# extension_board_0_2.net
KiCad netlist of a schematic drawn in EAGLE
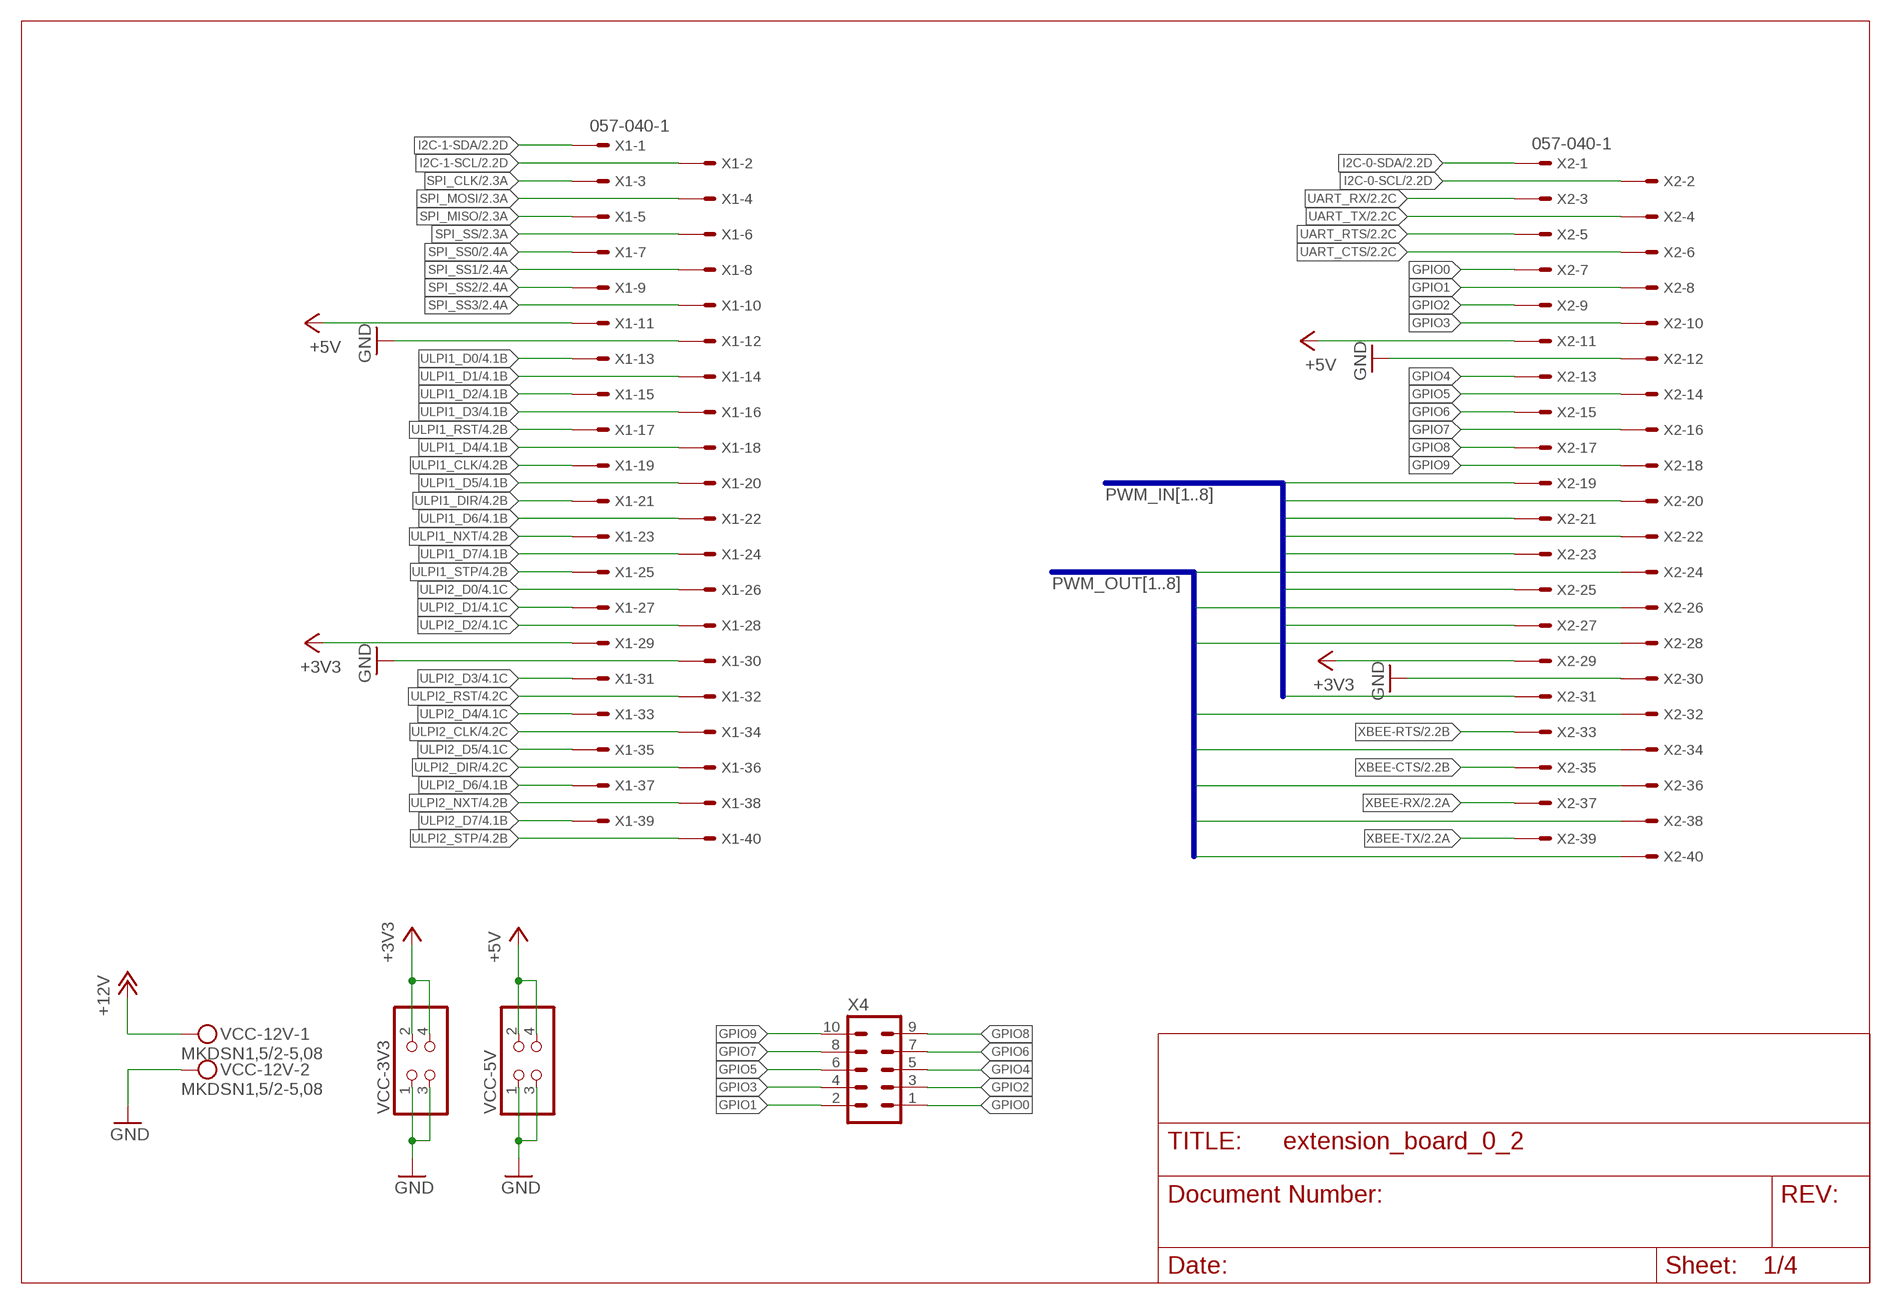
[diagram p0: schematic, sheet 1]
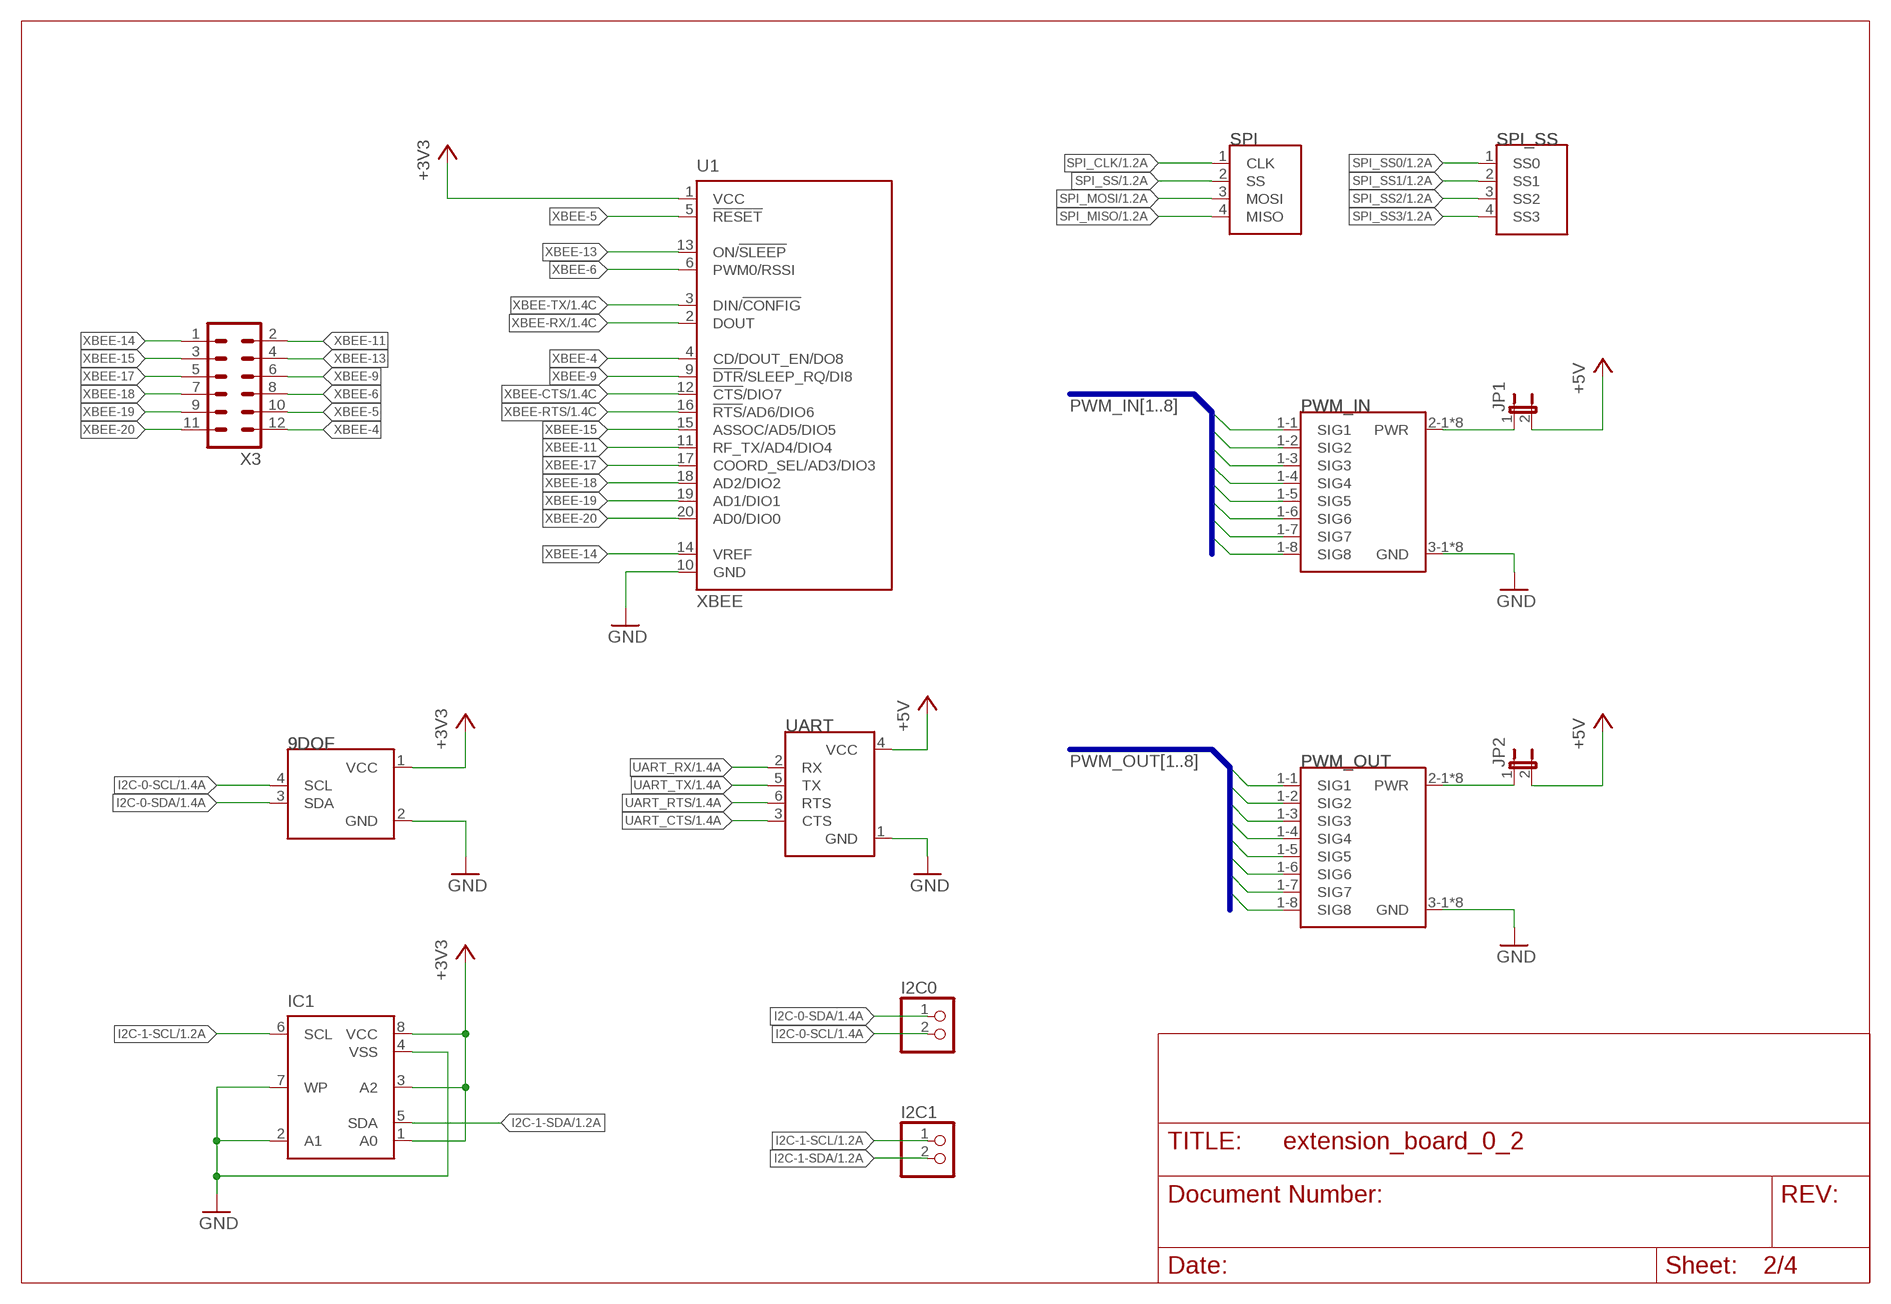
[diagram p1: schematic, sheet 2]
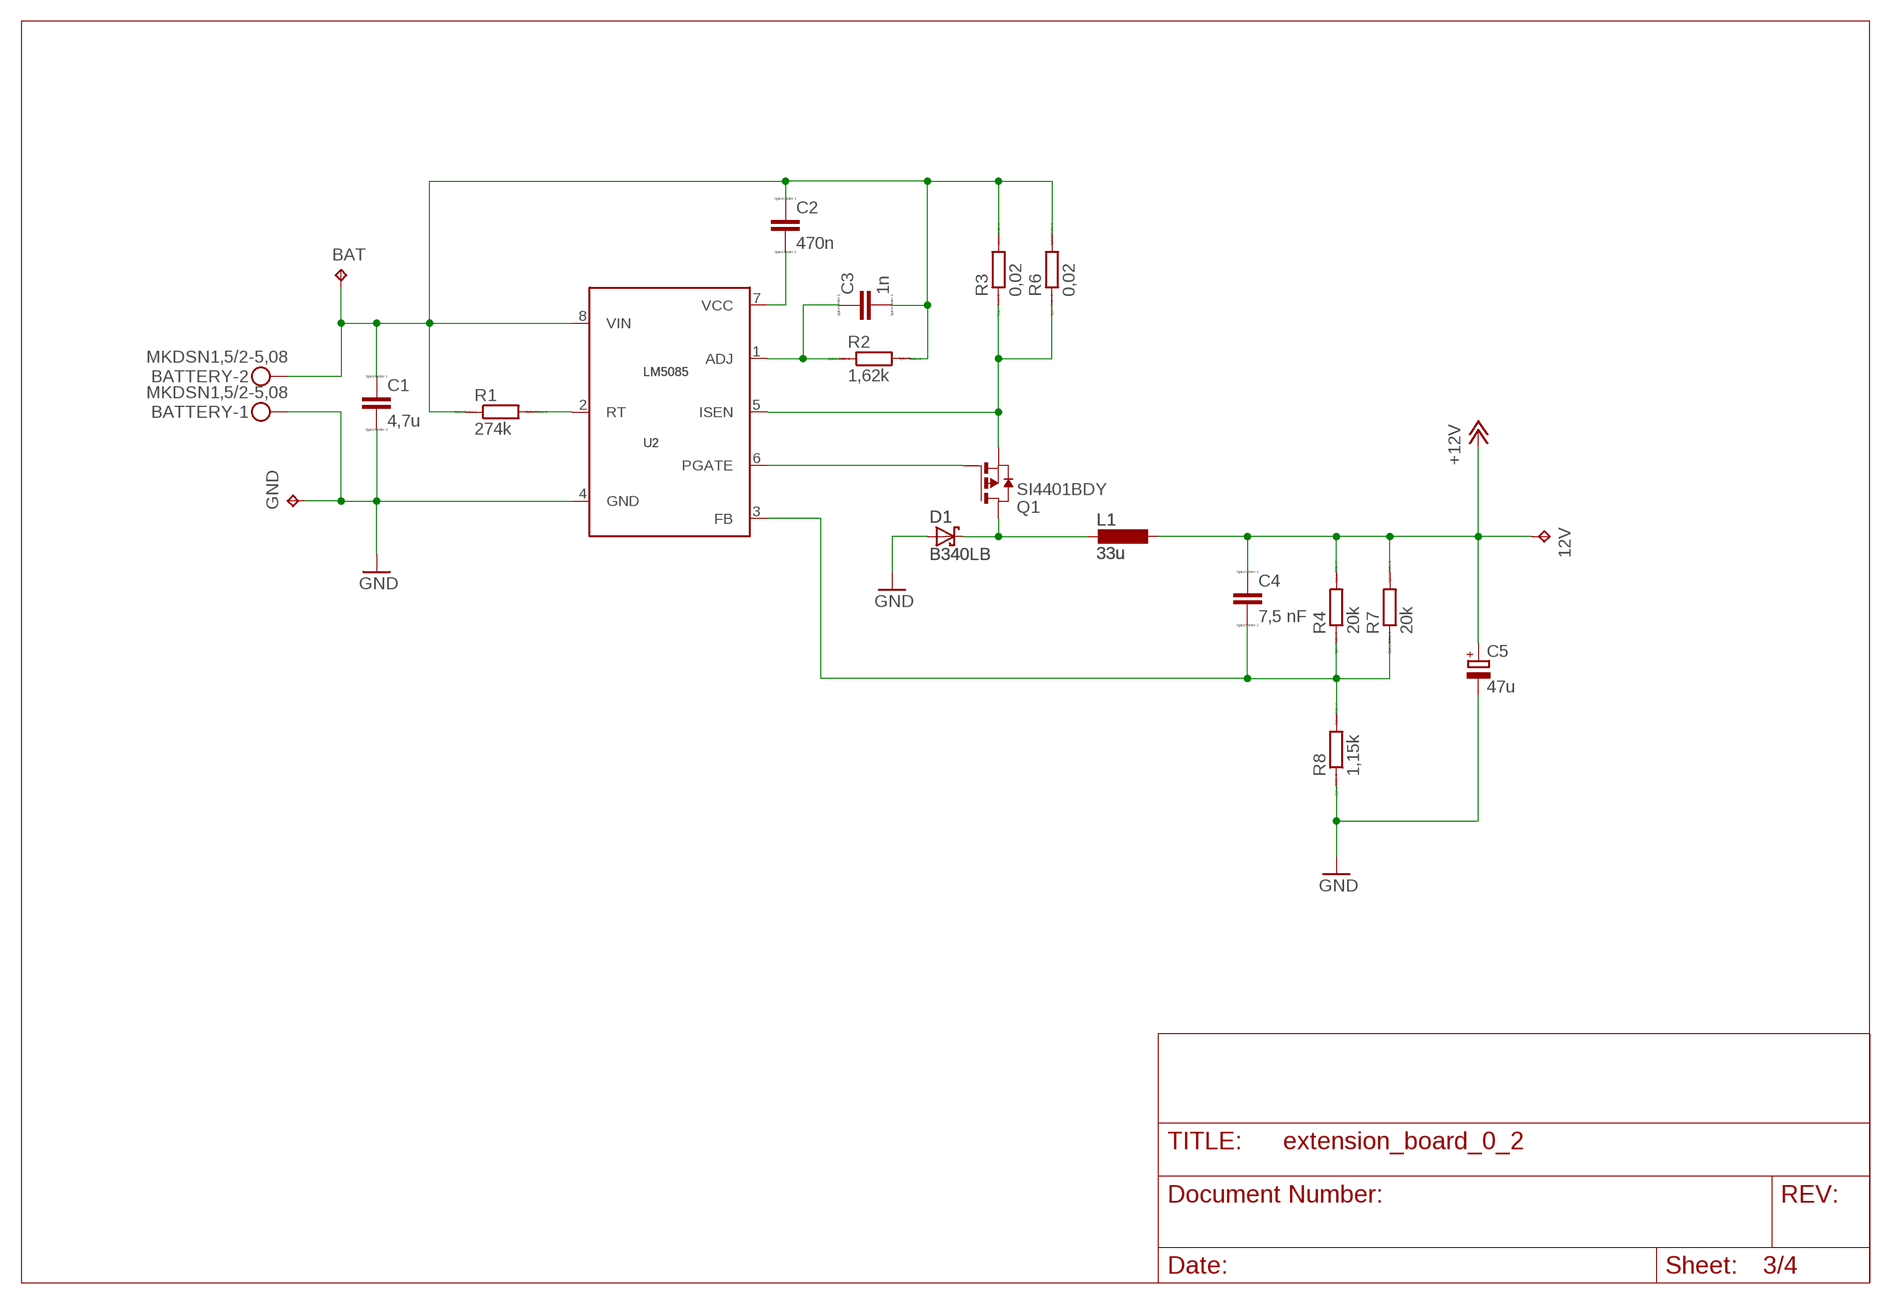
[diagram p2: schematic, sheet 3]
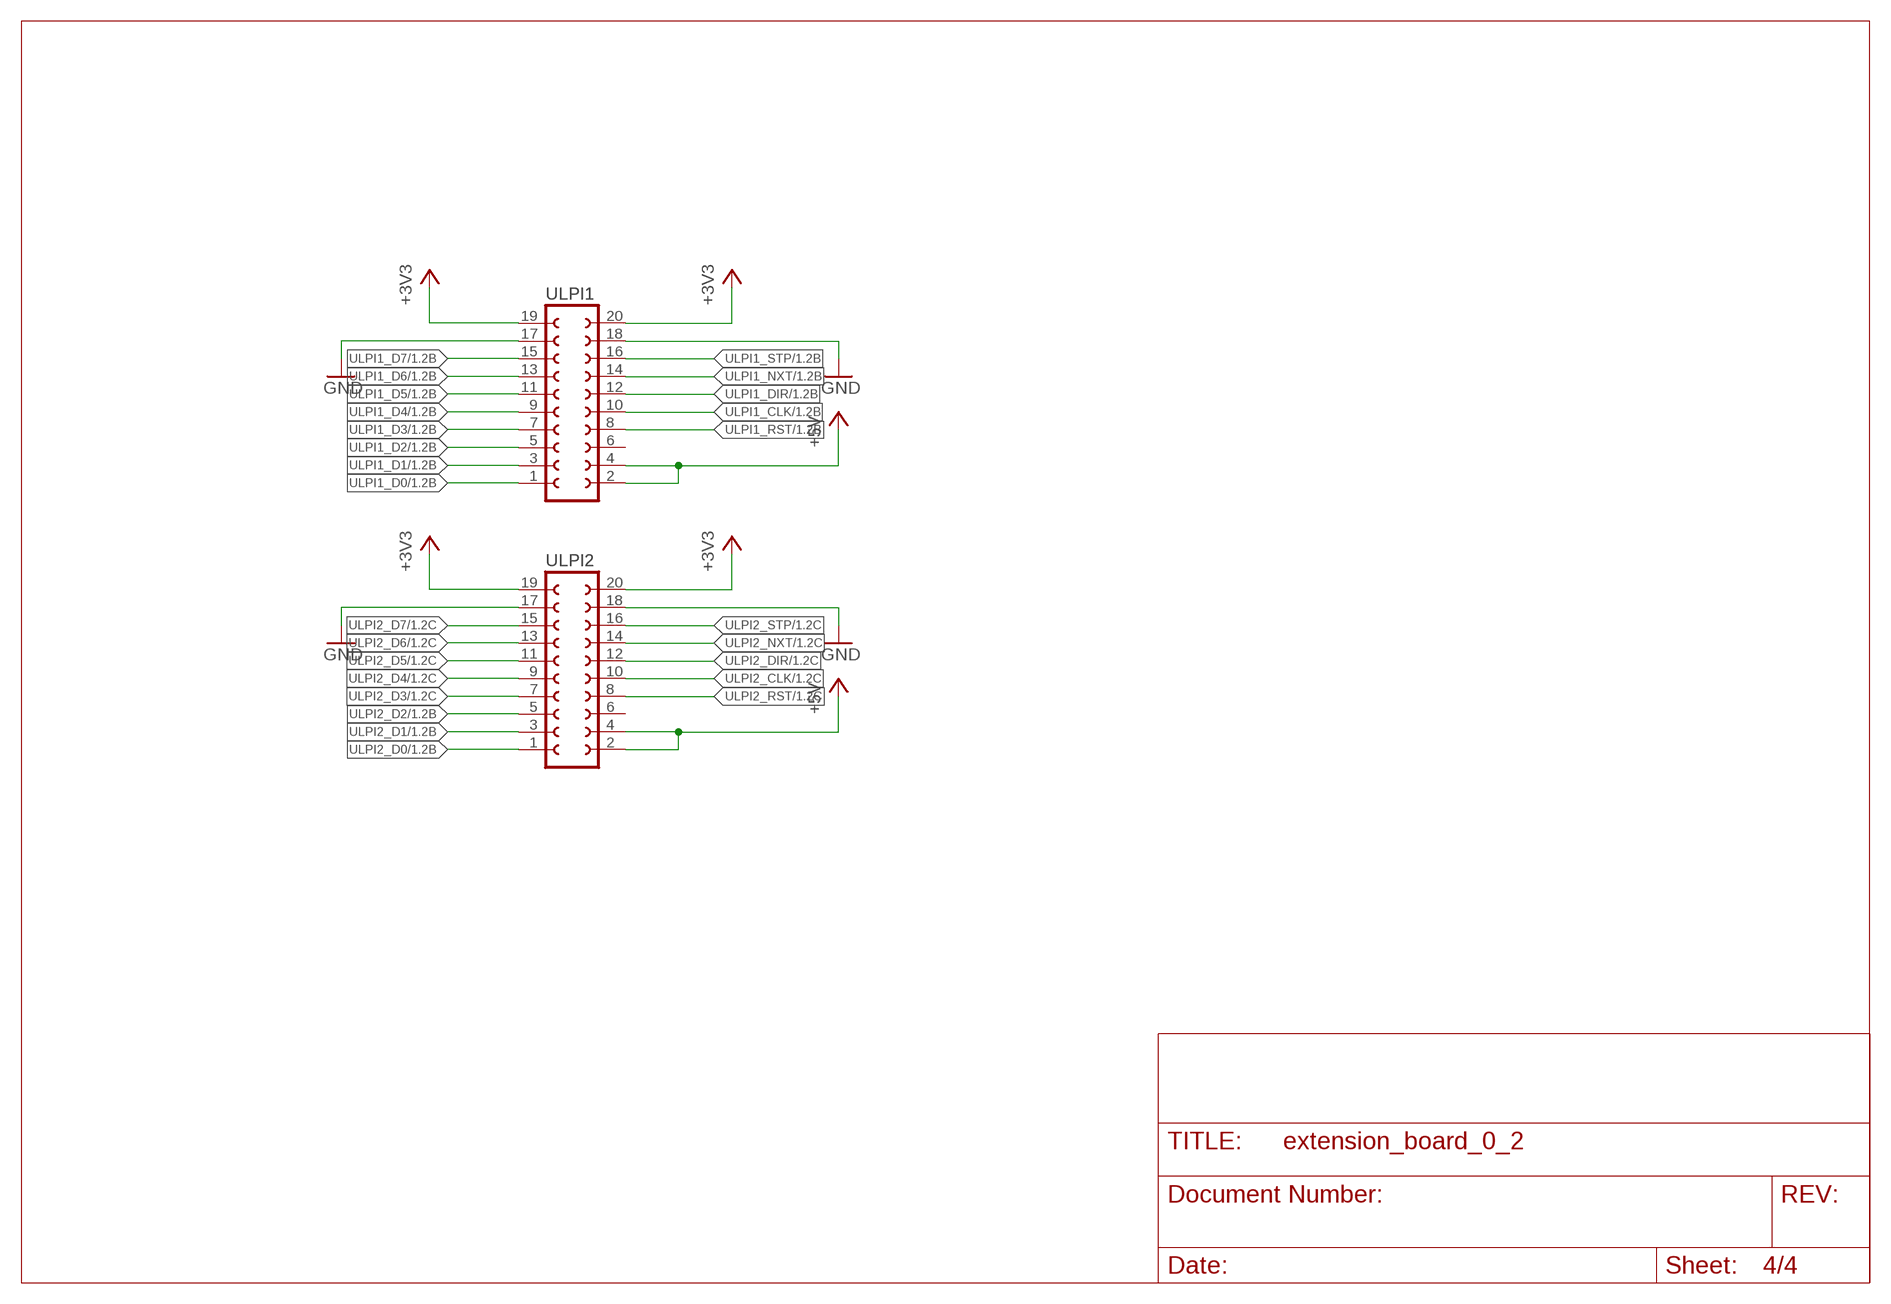
[diagram p3: schematic, sheet 4]

(export (version "E")
  (design (tool "Eeschema 10.0.6"))
  (components
    (comp (ref "9DOF")
      (value "I2C")
      (footprint "eagle-import:MA04-1")
      (libsource (lib "eagle-import") (part "I2C"))
    )
    (comp (ref "I2C0")
      (value "PINHD-1X2")
      (footprint "eagle-import:1X02")
      (libsource (lib "eagle-import") (part "PINHD-1X2"))
    )
    (comp (ref "I2C1")
      (value "PINHD-1X2")
      (footprint "eagle-import:1X02")
      (libsource (lib "eagle-import") (part "PINHD-1X2"))
    )
    (comp (ref "IC1")
      (value "NE555")
      (footprint "eagle-import:DIL-08")
      (libsource (lib "eagle-import") (part "NE555"))
    )
    (comp (ref "JP1")
      (value "JP1E")
      (footprint "eagle-import:JP1")
      (libsource (lib "eagle-import") (part "JP1E"))
    )
    (comp (ref "JP2")
      (value "JP1E")
      (footprint "eagle-import:JP1")
      (libsource (lib "eagle-import") (part "JP1E"))
    )
    (comp (ref "PWM_IN")
      (value "8RX")
      (footprint "eagle-import:MA08-3")
      (libsource (lib "eagle-import") (part "8RX"))
    )
    (comp (ref "PWM_OUT")
      (value "8RX")
      (footprint "eagle-import:MA08-3")
      (libsource (lib "eagle-import") (part "8RX"))
    )
    (comp (ref "SPI")
      (value "SPI_MAIN")
      (footprint "eagle-import:MA04-1")
      (libsource (lib "eagle-import") (part "SPI_MAIN"))
    )
    (comp (ref "SPI_SS")
      (value "SPI_SS")
      (footprint "eagle-import:MA04-1")
      (libsource (lib "eagle-import") (part "SPI_SS"))
    )
    (comp (ref "U1")
      (value "XBEE")
      (footprint "eagle-import:XBEE")
      (fields (field (name "MPN") "XBP24-Z7UIT-004"))
      (libsource (lib "eagle-import") (part "XBEE"))
    )
    (comp (ref "UART")
      (value "UART")
      (footprint "eagle-import:MA03-2")
      (libsource (lib "eagle-import") (part "UART"))
    )
    (comp (ref "X3")
      (value "MA06-2")
      (footprint "eagle-import:MA06-2")
      (libsource (lib "eagle-import") (part "MA06-2"))
    )
    (comp (ref "VCC-3V3")
      (value "PINHD-2X2")
      (footprint "eagle-import:2X02")
      (libsource (lib "eagle-import") (part "PINHD-2X2"))
    )
    (comp (ref "VCC-5V")
      (value "PINHD-2X2")
      (footprint "eagle-import:2X02")
      (libsource (lib "eagle-import") (part "PINHD-2X2"))
    )
    (comp (ref "VCC-12V")
      (value "MKDSN1,5/2-5,08")
      (footprint "eagle-import:MKDSN1,5_2-5,08")
      (fields (field (name "MPN") "MKDSN 1,5/2-5.08"))
      (libsource (lib "eagle-import") (part "MKDSN1,5/2-5,08"))
    )
    (comp (ref "X1")
      (value "057-040-1")
      (footprint "eagle-import:057-040-1")
      (libsource (lib "eagle-import") (part "057-040-1"))
    )
    (comp (ref "X2")
      (value "057-040-1")
      (footprint "eagle-import:057-040-1")
      (libsource (lib "eagle-import") (part "057-040-1"))
    )
    (comp (ref "X4")
      (value "MA05-2")
      (footprint "eagle-import:MA05-2")
      (libsource (lib "eagle-import") (part "MA05-2"))
    )
    (comp (ref "12V")
      (value "TPPAD1-13")
      (footprint "eagle-import:P1-13")
      (libsource (lib "eagle-import") (part "TPPAD1-13"))
    )
    (comp (ref "BAT")
      (value "TPPAD1-13")
      (footprint "eagle-import:P1-13")
      (libsource (lib "eagle-import") (part "TPPAD1-13"))
    )
    (comp (ref "BATTERY")
      (value "MKDSN1,5/2-5,08")
      (footprint "eagle-import:MKDSN1,5_2-5,08")
      (fields (field (name "MPN") "MKDSN 1,5/2-5.08"))
      (libsource (lib "eagle-import") (part "MKDSN1,5/2-5,08"))
    )
    (comp (ref "C1")
      (value "4,7u")
      (footprint "eagle-import:C0805")
      (libsource (lib "eagle-import") (part "C"))
    )
    (comp (ref "C2")
      (value "470n")
      (footprint "eagle-import:C1206")
      (libsource (lib "eagle-import") (part "CC1206"))
    )
    (comp (ref "C3")
      (value "1n")
      (footprint "eagle-import:C1206")
      (libsource (lib "eagle-import") (part "CC1206"))
    )
    (comp (ref "C4")
      (value "7,5 nF")
      (footprint "eagle-import:C0603")
      (libsource (lib "eagle-import") (part "CC0603"))
    )
    (comp (ref "C5")
      (value "47u")
      (footprint "eagle-import:CT3216")
      (libsource (lib "eagle-import") (part "CPOL-EUCT3216"))
    )
    (comp (ref "D1")
      (value "B340LB")
      (footprint "eagle-import:SMB")
      (libsource (lib "eagle-import") (part "B340LB"))
    )
    (comp (ref "GND")
      (value "TPPAD1-13")
      (footprint "eagle-import:P1-13")
      (libsource (lib "eagle-import") (part "TPPAD1-13"))
    )
    (comp (ref "L1")
      (value "33u")
      (footprint "eagle-import:INDUKTOR")
      (libsource (lib "eagle-import") (part "MSS1210"))
    )
    (comp (ref "Q1")
      (value "SI4401BDY")
      (footprint "eagle-import:SO8-FET")
      (libsource (lib "eagle-import") (part "SI4401BDY"))
    )
    (comp (ref "R1")
      (value "274k")
      (footprint "eagle-import:R1206")
      (libsource (lib "eagle-import") (part "RR1206"))
    )
    (comp (ref "R2")
      (value "1,62k")
      (footprint "eagle-import:R0805")
      (libsource (lib "eagle-import") (part "R"))
    )
    (comp (ref "R3")
      (value "0,02")
      (footprint "eagle-import:R1206")
      (libsource (lib "eagle-import") (part "RR1206"))
    )
    (comp (ref "R4")
      (value "20k")
      (footprint "eagle-import:R1206")
      (libsource (lib "eagle-import") (part "RR1206"))
    )
    (comp (ref "R6")
      (value "0,02")
      (footprint "eagle-import:R1206")
      (libsource (lib "eagle-import") (part "RR1206"))
    )
    (comp (ref "R7")
      (value "20k")
      (footprint "eagle-import:R1206")
      (libsource (lib "eagle-import") (part "RR1206"))
    )
    (comp (ref "R8")
      (value "1,15k")
      (footprint "eagle-import:R0805")
      (libsource (lib "eagle-import") (part "R"))
    )
    (comp (ref "U2")
      (value "LM5085")
      (footprint "eagle-import:S-PDSO-G08")
      (libsource (lib "eagle-import") (part "LM5085"))
    )
    (comp (ref "ULPI1")
      (value "FE10-2W")
      (footprint "eagle-import:FE10-2W")
      (libsource (lib "eagle-import") (part "FE10-2W"))
    )
    (comp (ref "ULPI2")
      (value "FE10-2W")
      (footprint "eagle-import:FE10-2W")
      (libsource (lib "eagle-import") (part "FE10-2W"))
    )
  )
  (nets
    (net (code "1") (name "+3V3") (class "Default")
      (node (ref "9DOF") (pin "1") (pinfunction "VCC_1") (pintype "power_in"))
      (node (ref "IC1") (pin "1") (pinfunction "A0_1") (pintype "input"))
      (node (ref "IC1") (pin "3") (pinfunction "A2_3") (pintype "input"))
      (node (ref "IC1") (pin "8") (pinfunction "VCC_8") (pintype "power_in"))
      (node (ref "U1") (pin "1") (pinfunction "VCC_1") (pintype "power_in"))
      (node (ref "ULPI1") (pin "19") (pinfunction "19_19") (pintype "passive"))
      (node (ref "ULPI1") (pin "20") (pinfunction "20_20") (pintype "passive"))
      (node (ref "ULPI2") (pin "19") (pinfunction "19_19") (pintype "passive"))
      (node (ref "ULPI2") (pin "20") (pinfunction "20_20") (pintype "passive"))
      (node (ref "VCC-3V3") (pin "2") (pinfunction "2_2") (pintype "passive"))
      (node (ref "VCC-3V3") (pin "4") (pinfunction "4_4") (pintype "passive"))
      (node (ref "X1") (pin "29") (pinfunction "S_29") (pintype "passive"))
      (node (ref "X2") (pin "29") (pinfunction "S_29") (pintype "passive"))
    )
    (net (code "2") (name "+5V") (class "Default")
      (node (ref "JP1") (pin "2") (pinfunction "2_2") (pintype "passive"))
      (node (ref "JP2") (pin "2") (pinfunction "2_2") (pintype "passive"))
      (node (ref "UART") (pin "4") (pinfunction "VCC_4") (pintype "bidirectional"))
      (node (ref "ULPI1") (pin "2") (pinfunction "2_2") (pintype "passive"))
      (node (ref "ULPI1") (pin "4") (pinfunction "4_4") (pintype "passive"))
      (node (ref "ULPI2") (pin "2") (pinfunction "2_2") (pintype "passive"))
      (node (ref "ULPI2") (pin "4") (pinfunction "4_4") (pintype "passive"))
      (node (ref "VCC-5V") (pin "2") (pinfunction "2_2") (pintype "passive"))
      (node (ref "VCC-5V") (pin "4") (pinfunction "4_4") (pintype "passive"))
      (node (ref "X1") (pin "11") (pinfunction "S_11") (pintype "passive"))
      (node (ref "X2") (pin "11") (pinfunction "S_11") (pintype "passive"))
    )
    (net (code "3") (name "+12V") (class "Default")
      (node (ref "12V") (pin "TP") (pinfunction "TP_TP") (pintype "input"))
      (node (ref "C4") (pin "1") (pinfunction "1_1") (pintype "passive"))
      (node (ref "C5") (pin "+") (pinfunction "+_+") (pintype "passive"))
      (node (ref "L1") (pin "P$2") (pinfunction "2_P$2") (pintype "passive"))
      (node (ref "R4") (pin "2") (pinfunction "2_2") (pintype "passive"))
      (node (ref "R7") (pin "2") (pinfunction "2_2") (pintype "passive"))
      (node (ref "VCC-12V") (pin "1") (pinfunction "KL_1") (pintype "passive"))
    )
    (net (code "8") (name "GND") (class "Default")
      (node (ref "9DOF") (pin "2") (pinfunction "GND_2") (pintype "power_in"))
      (node (ref "BATTERY") (pin "1") (pinfunction "KL_1") (pintype "passive"))
      (node (ref "C1") (pin "2") (pinfunction "2_2") (pintype "passive"))
      (node (ref "C5") (pin "-") (pinfunction "-_-") (pintype "passive"))
      (node (ref "D1") (pin "A") (pinfunction "A_A") (pintype "passive"))
      (node (ref "GND") (pin "TP") (pinfunction "TP_TP") (pintype "input"))
      (node (ref "IC1") (pin "2") (pinfunction "A1_2") (pintype "input"))
      (node (ref "IC1") (pin "4") (pinfunction "VSS_4") (pintype "power_in"))
      (node (ref "IC1") (pin "7") (pinfunction "WP_7") (pintype "input"))
      (node (ref "PWM_IN") (pin "3-1") (pinfunction "GND_3-1") (pintype "power_in"))
      (node (ref "PWM_IN") (pin "3-2") (pinfunction "GND_3-2") (pintype "power_in"))
      (node (ref "PWM_IN") (pin "3-3") (pinfunction "GND_3-3") (pintype "power_in"))
      (node (ref "PWM_IN") (pin "3-4") (pinfunction "GND_3-4") (pintype "power_in"))
      (node (ref "PWM_IN") (pin "3-5") (pinfunction "GND_3-5") (pintype "power_in"))
      (node (ref "PWM_IN") (pin "3-6") (pinfunction "GND_3-6") (pintype "power_in"))
      (node (ref "PWM_IN") (pin "3-7") (pinfunction "GND_3-7") (pintype "power_in"))
      (node (ref "PWM_IN") (pin "3-8") (pinfunction "GND_3-8") (pintype "power_in"))
      (node (ref "PWM_OUT") (pin "3-1") (pinfunction "GND_3-1") (pintype "power_in"))
      (node (ref "PWM_OUT") (pin "3-2") (pinfunction "GND_3-2") (pintype "power_in"))
      (node (ref "PWM_OUT") (pin "3-3") (pinfunction "GND_3-3") (pintype "power_in"))
      (node (ref "PWM_OUT") (pin "3-4") (pinfunction "GND_3-4") (pintype "power_in"))
      (node (ref "PWM_OUT") (pin "3-5") (pinfunction "GND_3-5") (pintype "power_in"))
      (node (ref "PWM_OUT") (pin "3-6") (pinfunction "GND_3-6") (pintype "power_in"))
      (node (ref "PWM_OUT") (pin "3-7") (pinfunction "GND_3-7") (pintype "power_in"))
      (node (ref "PWM_OUT") (pin "3-8") (pinfunction "GND_3-8") (pintype "power_in"))
      (node (ref "R8") (pin "1") (pinfunction "1_1") (pintype "passive"))
      (node (ref "U1") (pin "10") (pinfunction "GND_10") (pintype "power_in"))
      (node (ref "U2") (pin "4") (pinfunction "GND_4") (pintype "power_in"))
      (node (ref "UART") (pin "1") (pinfunction "GND_1") (pintype "bidirectional"))
      (node (ref "ULPI1") (pin "17") (pinfunction "17_17") (pintype "passive"))
      (node (ref "ULPI1") (pin "18") (pinfunction "18_18") (pintype "passive"))
      (node (ref "ULPI2") (pin "17") (pinfunction "17_17") (pintype "passive"))
      (node (ref "ULPI2") (pin "18") (pinfunction "18_18") (pintype "passive"))
      (node (ref "VCC-12V") (pin "2") (pinfunction "KL_2") (pintype "passive"))
      (node (ref "VCC-3V3") (pin "1") (pinfunction "1_1") (pintype "passive"))
      (node (ref "VCC-3V3") (pin "3") (pinfunction "3_3") (pintype "passive"))
      (node (ref "VCC-5V") (pin "1") (pinfunction "1_1") (pintype "passive"))
      (node (ref "VCC-5V") (pin "3") (pinfunction "3_3") (pintype "passive"))
      (node (ref "X1") (pin "12") (pinfunction "S_12") (pintype "passive"))
      (node (ref "X1") (pin "30") (pinfunction "S_30") (pintype "passive"))
      (node (ref "X2") (pin "12") (pinfunction "S_12") (pintype "passive"))
      (node (ref "X2") (pin "30") (pinfunction "S_30") (pintype "passive"))
    )
    (net (code "9") (name "GPIO0") (class "Default")
      (node (ref "X2") (pin "7") (pinfunction "S_7") (pintype "passive"))
      (node (ref "X4") (pin "1") (pinfunction "1_1") (pintype "passive"))
    )
    (net (code "10") (name "GPIO1") (class "Default")
      (node (ref "X2") (pin "8") (pinfunction "S_8") (pintype "passive"))
      (node (ref "X4") (pin "2") (pinfunction "2_2") (pintype "passive"))
    )
    (net (code "11") (name "GPIO2") (class "Default")
      (node (ref "X2") (pin "9") (pinfunction "S_9") (pintype "passive"))
      (node (ref "X4") (pin "3") (pinfunction "3_3") (pintype "passive"))
    )
    (net (code "12") (name "GPIO3") (class "Default")
      (node (ref "X2") (pin "10") (pinfunction "S_10") (pintype "passive"))
      (node (ref "X4") (pin "4") (pinfunction "4_4") (pintype "passive"))
    )
    (net (code "13") (name "GPIO4") (class "Default")
      (node (ref "X2") (pin "13") (pinfunction "S_13") (pintype "passive"))
      (node (ref "X4") (pin "5") (pinfunction "5_5") (pintype "passive"))
    )
    (net (code "14") (name "GPIO5") (class "Default")
      (node (ref "X2") (pin "14") (pinfunction "S_14") (pintype "passive"))
      (node (ref "X4") (pin "6") (pinfunction "6_6") (pintype "passive"))
    )
    (net (code "15") (name "GPIO6") (class "Default")
      (node (ref "X2") (pin "15") (pinfunction "S_15") (pintype "passive"))
      (node (ref "X4") (pin "7") (pinfunction "7_7") (pintype "passive"))
    )
    (net (code "16") (name "GPIO7") (class "Default")
      (node (ref "X2") (pin "16") (pinfunction "S_16") (pintype "passive"))
      (node (ref "X4") (pin "8") (pinfunction "8_8") (pintype "passive"))
    )
    (net (code "17") (name "GPIO8") (class "Default")
      (node (ref "X2") (pin "17") (pinfunction "S_17") (pintype "passive"))
      (node (ref "X4") (pin "9") (pinfunction "9_9") (pintype "passive"))
    )
    (net (code "18") (name "GPIO9") (class "Default")
      (node (ref "X2") (pin "18") (pinfunction "S_18") (pintype "passive"))
      (node (ref "X4") (pin "10") (pinfunction "10_10") (pintype "passive"))
    )
    (net (code "19") (name "I2C-0-SCL") (class "Default")
      (node (ref "9DOF") (pin "4") (pinfunction "SCL_4") (pintype "bidirectional"))
      (node (ref "I2C0") (pin "2") (pinfunction "2_2") (pintype "passive"))
      (node (ref "X2") (pin "2") (pinfunction "S_2") (pintype "passive"))
    )
    (net (code "20") (name "I2C-0-SDA") (class "Default")
      (node (ref "9DOF") (pin "3") (pinfunction "SDA_3") (pintype "bidirectional"))
      (node (ref "I2C0") (pin "1") (pinfunction "1_1") (pintype "passive"))
      (node (ref "X2") (pin "1") (pinfunction "S_1") (pintype "passive"))
    )
    (net (code "21") (name "I2C-1-SCL") (class "Default")
      (node (ref "I2C1") (pin "1") (pinfunction "1_1") (pintype "passive"))
      (node (ref "IC1") (pin "6") (pinfunction "SCL_6") (pintype "bidirectional"))
      (node (ref "X1") (pin "2") (pinfunction "S_2") (pintype "passive"))
    )
    (net (code "22") (name "I2C-1-SDA") (class "Default")
      (node (ref "I2C1") (pin "2") (pinfunction "2_2") (pintype "passive"))
      (node (ref "IC1") (pin "5") (pinfunction "SDA_5") (pintype "bidirectional"))
      (node (ref "X1") (pin "1") (pinfunction "S_1") (pintype "passive"))
    )
    (net (code "23") (name "Net-(BATTERYB-KL)") (class "Default")
      (node (ref "BAT") (pin "TP") (pinfunction "TP_TP") (pintype "input"))
      (node (ref "BATTERY") (pin "2") (pinfunction "KL_2") (pintype "passive"))
      (node (ref "C1") (pin "1") (pinfunction "1_1") (pintype "passive"))
      (node (ref "C2") (pin "1") (pinfunction "1_1") (pintype "passive"))
      (node (ref "C3") (pin "2") (pinfunction "2_2") (pintype "passive"))
      (node (ref "R1") (pin "1") (pinfunction "1_1") (pintype "passive"))
      (node (ref "R2") (pin "2") (pinfunction "2_2") (pintype "passive"))
      (node (ref "R3") (pin "2") (pinfunction "2_2") (pintype "passive"))
      (node (ref "R6") (pin "2") (pinfunction "2_2") (pintype "passive"))
      (node (ref "U2") (pin "8") (pinfunction "VIN_8") (pintype "input"))
    )
    (net (code "24") (name "Net-(JP1-Pad1)") (class "Default")
      (node (ref "JP1") (pin "1") (pinfunction "1_1") (pintype "passive"))
      (node (ref "PWM_IN") (pin "2-1") (pinfunction "PWR_2-1") (pintype "power_in"))
      (node (ref "PWM_IN") (pin "2-2") (pinfunction "PWR_2-2") (pintype "power_in"))
      (node (ref "PWM_IN") (pin "2-3") (pinfunction "PWR_2-3") (pintype "power_in"))
      (node (ref "PWM_IN") (pin "2-4") (pinfunction "PWR_2-4") (pintype "power_in"))
      (node (ref "PWM_IN") (pin "2-5") (pinfunction "PWR_2-5") (pintype "power_in"))
      (node (ref "PWM_IN") (pin "2-6") (pinfunction "PWR_2-6") (pintype "power_in"))
      (node (ref "PWM_IN") (pin "2-7") (pinfunction "PWR_2-7") (pintype "power_in"))
      (node (ref "PWM_IN") (pin "2-8") (pinfunction "PWR_2-8") (pintype "power_in"))
    )
    (net (code "25") (name "Net-(JP2-Pad1)") (class "Default")
      (node (ref "JP2") (pin "1") (pinfunction "1_1") (pintype "passive"))
      (node (ref "PWM_OUT") (pin "2-1") (pinfunction "PWR_2-1") (pintype "power_in"))
      (node (ref "PWM_OUT") (pin "2-2") (pinfunction "PWR_2-2") (pintype "power_in"))
      (node (ref "PWM_OUT") (pin "2-3") (pinfunction "PWR_2-3") (pintype "power_in"))
      (node (ref "PWM_OUT") (pin "2-4") (pinfunction "PWR_2-4") (pintype "power_in"))
      (node (ref "PWM_OUT") (pin "2-5") (pinfunction "PWR_2-5") (pintype "power_in"))
      (node (ref "PWM_OUT") (pin "2-6") (pinfunction "PWR_2-6") (pintype "power_in"))
      (node (ref "PWM_OUT") (pin "2-7") (pinfunction "PWR_2-7") (pintype "power_in"))
      (node (ref "PWM_OUT") (pin "2-8") (pinfunction "PWR_2-8") (pintype "power_in"))
    )
    (net (code "26") (name "Net-(L1-1)") (class "Default")
      (node (ref "D1") (pin "C") (pinfunction "C_C") (pintype "passive"))
      (node (ref "L1") (pin "P$1") (pinfunction "1_P$1") (pintype "passive"))
      (node (ref "Q1") (pin "5") (pinfunction "D_5") (pintype "passive"))
      (node (ref "Q1") (pin "6") (pinfunction "D_6") (pintype "passive"))
      (node (ref "Q1") (pin "7") (pinfunction "D_7") (pintype "passive"))
      (node (ref "Q1") (pin "8") (pinfunction "D_8") (pintype "passive"))
      (node (ref "Q1") (pin "D1") (pinfunction "D_D1") (pintype "passive"))
      (node (ref "Q1") (pin "D2") (pinfunction "D_D2") (pintype "passive"))
      (node (ref "Q1") (pin "D3") (pinfunction "D_D3") (pintype "passive"))
    )
    (net (code "27") (name "Net-(Q1-G)") (class "Default")
      (node (ref "Q1") (pin "4") (pinfunction "G_4") (pintype "passive"))
      (node (ref "U2") (pin "6") (pinfunction "PGATE_6") (pintype "bidirectional"))
    )
    (net (code "28") (name "Net-(U2-ADJ)") (class "Default")
      (node (ref "C3") (pin "1") (pinfunction "1_1") (pintype "passive"))
      (node (ref "R2") (pin "1") (pinfunction "1_1") (pintype "passive"))
      (node (ref "U2") (pin "1") (pinfunction "ADJ_1") (pintype "bidirectional"))
    )
    (net (code "29") (name "Net-(U2-FB)") (class "Default")
      (node (ref "C4") (pin "2") (pinfunction "2_2") (pintype "passive"))
      (node (ref "R4") (pin "1") (pinfunction "1_1") (pintype "passive"))
      (node (ref "R7") (pin "1") (pinfunction "1_1") (pintype "passive"))
      (node (ref "R8") (pin "2") (pinfunction "2_2") (pintype "passive"))
      (node (ref "U2") (pin "3") (pinfunction "FB_3") (pintype "bidirectional"))
    )
    (net (code "30") (name "Net-(U2-ISEN)") (class "Default")
      (node (ref "Q1") (pin "1") (pinfunction "S_1") (pintype "passive"))
      (node (ref "Q1") (pin "2") (pinfunction "S_2") (pintype "passive"))
      (node (ref "Q1") (pin "3") (pinfunction "S_3") (pintype "passive"))
      (node (ref "R3") (pin "1") (pinfunction "1_1") (pintype "passive"))
      (node (ref "R6") (pin "1") (pinfunction "1_1") (pintype "passive"))
      (node (ref "U2") (pin "5") (pinfunction "ISEN_5") (pintype "bidirectional"))
    )
    (net (code "31") (name "Net-(U2-RT)") (class "Default")
      (node (ref "R1") (pin "2") (pinfunction "2_2") (pintype "passive"))
      (node (ref "U2") (pin "2") (pinfunction "RT_2") (pintype "bidirectional"))
    )
    (net (code "32") (name "Net-(U2-VCC)") (class "Default")
      (node (ref "C2") (pin "2") (pinfunction "2_2") (pintype "passive"))
      (node (ref "U2") (pin "7") (pinfunction "VCC_7") (pintype "power_in"))
    )
    (net (code "33") (name "PWM_IN1") (class "Default")
      (node (ref "PWM_IN") (pin "1-1") (pinfunction "SIG1_1-1") (pintype "bidirectional"))
      (node (ref "X2") (pin "19") (pinfunction "S_19") (pintype "passive"))
    )
    (net (code "34") (name "PWM_IN2") (class "Default")
      (node (ref "PWM_IN") (pin "1-2") (pinfunction "SIG2_1-2") (pintype "bidirectional"))
      (node (ref "X2") (pin "20") (pinfunction "S_20") (pintype "passive"))
    )
    (net (code "35") (name "PWM_IN3") (class "Default")
      (node (ref "PWM_IN") (pin "1-3") (pinfunction "SIG3_1-3") (pintype "bidirectional"))
      (node (ref "X2") (pin "21") (pinfunction "S_21") (pintype "passive"))
    )
    (net (code "36") (name "PWM_IN4") (class "Default")
      (node (ref "PWM_IN") (pin "1-4") (pinfunction "SIG4_1-4") (pintype "bidirectional"))
      (node (ref "X2") (pin "22") (pinfunction "S_22") (pintype "passive"))
    )
    (net (code "37") (name "PWM_IN5") (class "Default")
      (node (ref "PWM_IN") (pin "1-5") (pinfunction "SIG5_1-5") (pintype "bidirectional"))
      (node (ref "X2") (pin "23") (pinfunction "S_23") (pintype "passive"))
    )
    (net (code "38") (name "PWM_IN6") (class "Default")
      (node (ref "PWM_IN") (pin "1-6") (pinfunction "SIG6_1-6") (pintype "bidirectional"))
      (node (ref "X2") (pin "25") (pinfunction "S_25") (pintype "passive"))
    )
    (net (code "39") (name "PWM_IN7") (class "Default")
      (node (ref "PWM_IN") (pin "1-7") (pinfunction "SIG7_1-7") (pintype "bidirectional"))
      (node (ref "X2") (pin "27") (pinfunction "S_27") (pintype "passive"))
    )
    (net (code "40") (name "PWM_IN8") (class "Default")
      (node (ref "PWM_IN") (pin "1-8") (pinfunction "SIG8_1-8") (pintype "bidirectional"))
      (node (ref "X2") (pin "31") (pinfunction "S_31") (pintype "passive"))
    )
    (net (code "41") (name "PWM_OUT1") (class "Default")
      (node (ref "PWM_OUT") (pin "1-1") (pinfunction "SIG1_1-1") (pintype "bidirectional"))
      (node (ref "X2") (pin "40") (pinfunction "S_40") (pintype "passive"))
    )
    (net (code "42") (name "PWM_OUT2") (class "Default")
      (node (ref "PWM_OUT") (pin "1-2") (pinfunction "SIG2_1-2") (pintype "bidirectional"))
      (node (ref "X2") (pin "38") (pinfunction "S_38") (pintype "passive"))
    )
    (net (code "43") (name "PWM_OUT3") (class "Default")
      (node (ref "PWM_OUT") (pin "1-3") (pinfunction "SIG3_1-3") (pintype "bidirectional"))
      (node (ref "X2") (pin "36") (pinfunction "S_36") (pintype "passive"))
    )
    (net (code "44") (name "PWM_OUT4") (class "Default")
      (node (ref "PWM_OUT") (pin "1-4") (pinfunction "SIG4_1-4") (pintype "bidirectional"))
      (node (ref "X2") (pin "34") (pinfunction "S_34") (pintype "passive"))
    )
    (net (code "45") (name "PWM_OUT5") (class "Default")
      (node (ref "PWM_OUT") (pin "1-5") (pinfunction "SIG5_1-5") (pintype "bidirectional"))
      (node (ref "X2") (pin "32") (pinfunction "S_32") (pintype "passive"))
    )
    (net (code "46") (name "PWM_OUT6") (class "Default")
      (node (ref "PWM_OUT") (pin "1-6") (pinfunction "SIG6_1-6") (pintype "bidirectional"))
      (node (ref "X2") (pin "28") (pinfunction "S_28") (pintype "passive"))
    )
    (net (code "47") (name "PWM_OUT7") (class "Default")
      (node (ref "PWM_OUT") (pin "1-7") (pinfunction "SIG7_1-7") (pintype "bidirectional"))
      (node (ref "X2") (pin "26") (pinfunction "S_26") (pintype "passive"))
    )
    (net (code "48") (name "PWM_OUT8") (class "Default")
      (node (ref "PWM_OUT") (pin "1-8") (pinfunction "SIG8_1-8") (pintype "bidirectional"))
      (node (ref "X2") (pin "24") (pinfunction "S_24") (pintype "passive"))
    )
    (net (code "49") (name "SPI_CLK") (class "Default")
      (node (ref "SPI") (pin "1") (pinfunction "CLK_1") (pintype "bidirectional"))
      (node (ref "X1") (pin "3") (pinfunction "S_3") (pintype "passive"))
    )
    (net (code "50") (name "SPI_MISO") (class "Default")
      (node (ref "SPI") (pin "4") (pinfunction "MISO_4") (pintype "bidirectional"))
      (node (ref "X1") (pin "5") (pinfunction "S_5") (pintype "passive"))
    )
    (net (code "51") (name "SPI_MOSI") (class "Default")
      (node (ref "SPI") (pin "3") (pinfunction "MOSI_3") (pintype "bidirectional"))
      (node (ref "X1") (pin "4") (pinfunction "S_4") (pintype "passive"))
    )
    (net (code "52") (name "SPI_SS") (class "Default")
      (node (ref "SPI") (pin "2") (pinfunction "SS_2") (pintype "bidirectional"))
      (node (ref "X1") (pin "6") (pinfunction "S_6") (pintype "passive"))
    )
    (net (code "53") (name "SPI_SS0") (class "Default")
      (node (ref "SPI_SS") (pin "1") (pinfunction "SS0_1") (pintype "bidirectional"))
      (node (ref "X1") (pin "7") (pinfunction "S_7") (pintype "passive"))
    )
    (net (code "54") (name "SPI_SS1") (class "Default")
      (node (ref "SPI_SS") (pin "2") (pinfunction "SS1_2") (pintype "bidirectional"))
      (node (ref "X1") (pin "8") (pinfunction "S_8") (pintype "passive"))
    )
    (net (code "55") (name "SPI_SS2") (class "Default")
      (node (ref "SPI_SS") (pin "3") (pinfunction "SS2_3") (pintype "bidirectional"))
      (node (ref "X1") (pin "9") (pinfunction "S_9") (pintype "passive"))
    )
    (net (code "56") (name "SPI_SS3") (class "Default")
      (node (ref "SPI_SS") (pin "4") (pinfunction "SS3_4") (pintype "bidirectional"))
      (node (ref "X1") (pin "10") (pinfunction "S_10") (pintype "passive"))
    )
    (net (code "57") (name "UART_CTS") (class "Default")
      (node (ref "UART") (pin "3") (pinfunction "CTS_3") (pintype "bidirectional"))
      (node (ref "X2") (pin "6") (pinfunction "S_6") (pintype "passive"))
    )
    (net (code "58") (name "UART_RTS") (class "Default")
      (node (ref "UART") (pin "6") (pinfunction "RTS_6") (pintype "bidirectional"))
      (node (ref "X2") (pin "5") (pinfunction "S_5") (pintype "passive"))
    )
    (net (code "59") (name "UART_RX") (class "Default")
      (node (ref "UART") (pin "2") (pinfunction "RX_2") (pintype "bidirectional"))
      (node (ref "X2") (pin "3") (pinfunction "S_3") (pintype "passive"))
    )
    (net (code "60") (name "UART_TX") (class "Default")
      (node (ref "UART") (pin "5") (pinfunction "TX_5") (pintype "bidirectional"))
      (node (ref "X2") (pin "4") (pinfunction "S_4") (pintype "passive"))
    )
    (net (code "61") (name "ULPI1_CLK") (class "Default")
      (node (ref "ULPI1") (pin "10") (pinfunction "10_10") (pintype "passive"))
      (node (ref "X1") (pin "19") (pinfunction "S_19") (pintype "passive"))
    )
    (net (code "62") (name "ULPI1_D0") (class "Default")
      (node (ref "ULPI1") (pin "1") (pinfunction "1_1") (pintype "passive"))
      (node (ref "X1") (pin "13") (pinfunction "S_13") (pintype "passive"))
    )
    (net (code "63") (name "ULPI1_D1") (class "Default")
      (node (ref "ULPI1") (pin "3") (pinfunction "3_3") (pintype "passive"))
      (node (ref "X1") (pin "14") (pinfunction "S_14") (pintype "passive"))
    )
    (net (code "64") (name "ULPI1_D2") (class "Default")
      (node (ref "ULPI1") (pin "5") (pinfunction "5_5") (pintype "passive"))
      (node (ref "X1") (pin "15") (pinfunction "S_15") (pintype "passive"))
    )
    (net (code "65") (name "ULPI1_D3") (class "Default")
      (node (ref "ULPI1") (pin "7") (pinfunction "7_7") (pintype "passive"))
      (node (ref "X1") (pin "16") (pinfunction "S_16") (pintype "passive"))
    )
    (net (code "66") (name "ULPI1_D4") (class "Default")
      (node (ref "ULPI1") (pin "9") (pinfunction "9_9") (pintype "passive"))
      (node (ref "X1") (pin "18") (pinfunction "S_18") (pintype "passive"))
    )
    (net (code "67") (name "ULPI1_D5") (class "Default")
      (node (ref "ULPI1") (pin "11") (pinfunction "11_11") (pintype "passive"))
      (node (ref "X1") (pin "20") (pinfunction "S_20") (pintype "passive"))
    )
    (net (code "68") (name "ULPI1_D6") (class "Default")
      (node (ref "ULPI1") (pin "13") (pinfunction "13_13") (pintype "passive"))
      (node (ref "X1") (pin "22") (pinfunction "S_22") (pintype "passive"))
    )
    (net (code "69") (name "ULPI1_D7") (class "Default")
      (node (ref "ULPI1") (pin "15") (pinfunction "15_15") (pintype "passive"))
      (node (ref "X1") (pin "24") (pinfunction "S_24") (pintype "passive"))
    )
    (net (code "70") (name "ULPI1_DIR") (class "Default")
      (node (ref "ULPI1") (pin "12") (pinfunction "12_12") (pintype "passive"))
      (node (ref "X1") (pin "21") (pinfunction "S_21") (pintype "passive"))
    )
    (net (code "71") (name "ULPI1_NXT") (class "Default")
      (node (ref "ULPI1") (pin "14") (pinfunction "14_14") (pintype "passive"))
      (node (ref "X1") (pin "23") (pinfunction "S_23") (pintype "passive"))
    )
    (net (code "72") (name "ULPI1_RST") (class "Default")
      (node (ref "ULPI1") (pin "8") (pinfunction "8_8") (pintype "passive"))
      (node (ref "X1") (pin "17") (pinfunction "S_17") (pintype "passive"))
    )
    (net (code "73") (name "ULPI1_STP") (class "Default")
      (node (ref "ULPI1") (pin "16") (pinfunction "16_16") (pintype "passive"))
      (node (ref "X1") (pin "25") (pinfunction "S_25") (pintype "passive"))
    )
    (net (code "74") (name "ULPI2_CLK") (class "Default")
      (node (ref "ULPI2") (pin "10") (pinfunction "10_10") (pintype "passive"))
      (node (ref "X1") (pin "34") (pinfunction "S_34") (pintype "passive"))
    )
    (net (code "75") (name "ULPI2_D0") (class "Default")
      (node (ref "ULPI2") (pin "1") (pinfunction "1_1") (pintype "passive"))
      (node (ref "X1") (pin "26") (pinfunction "S_26") (pintype "passive"))
    )
    (net (code "76") (name "ULPI2_D1") (class "Default")
      (node (ref "ULPI2") (pin "3") (pinfunction "3_3") (pintype "passive"))
      (node (ref "X1") (pin "27") (pinfunction "S_27") (pintype "passive"))
    )
    (net (code "77") (name "ULPI2_D2") (class "Default")
      (node (ref "ULPI2") (pin "5") (pinfunction "5_5") (pintype "passive"))
      (node (ref "X1") (pin "28") (pinfunction "S_28") (pintype "passive"))
    )
    (net (code "78") (name "ULPI2_D3") (class "Default")
      (node (ref "ULPI2") (pin "7") (pinfunction "7_7") (pintype "passive"))
      (node (ref "X1") (pin "31") (pinfunction "S_31") (pintype "passive"))
    )
    (net (code "79") (name "ULPI2_D4") (class "Default")
      (node (ref "ULPI2") (pin "9") (pinfunction "9_9") (pintype "passive"))
      (node (ref "X1") (pin "33") (pinfunction "S_33") (pintype "passive"))
    )
    (net (code "80") (name "ULPI2_D5") (class "Default")
      (node (ref "ULPI2") (pin "11") (pinfunction "11_11") (pintype "passive"))
      (node (ref "X1") (pin "35") (pinfunction "S_35") (pintype "passive"))
    )
    (net (code "81") (name "ULPI2_D6") (class "Default")
      (node (ref "ULPI2") (pin "13") (pinfunction "13_13") (pintype "passive"))
      (node (ref "X1") (pin "37") (pinfunction "S_37") (pintype "passive"))
    )
    (net (code "82") (name "ULPI2_D7") (class "Default")
      (node (ref "ULPI2") (pin "15") (pinfunction "15_15") (pintype "passive"))
      (node (ref "X1") (pin "39") (pinfunction "S_39") (pintype "passive"))
    )
    (net (code "83") (name "ULPI2_DIR") (class "Default")
      (node (ref "ULPI2") (pin "12") (pinfunction "12_12") (pintype "passive"))
      (node (ref "X1") (pin "36") (pinfunction "S_36") (pintype "passive"))
    )
    (net (code "84") (name "ULPI2_NXT") (class "Default")
      (node (ref "ULPI2") (pin "14") (pinfunction "14_14") (pintype "passive"))
      (node (ref "X1") (pin "38") (pinfunction "S_38") (pintype "passive"))
    )
    (net (code "85") (name "ULPI2_RST") (class "Default")
      (node (ref "ULPI2") (pin "8") (pinfunction "8_8") (pintype "passive"))
      (node (ref "X1") (pin "32") (pinfunction "S_32") (pintype "passive"))
    )
    (net (code "86") (name "ULPI2_STP") (class "Default")
      (node (ref "ULPI2") (pin "16") (pinfunction "16_16") (pintype "passive"))
      (node (ref "X1") (pin "40") (pinfunction "S_40") (pintype "passive"))
    )
    (net (code "87") (name "XBEE-4") (class "Default")
      (node (ref "U1") (pin "4") (pinfunction "CD/DOUT_EN/DO8_4") (pintype "output"))
      (node (ref "X3") (pin "12") (pinfunction "12_12") (pintype "passive"))
    )
    (net (code "88") (name "XBEE-5") (class "Default")
      (node (ref "U1") (pin "5") (pinfunction "~{RESET}_5") (pintype "input"))
      (node (ref "X3") (pin "10") (pinfunction "10_10") (pintype "passive"))
    )
    (net (code "89") (name "XBEE-6") (class "Default")
      (node (ref "U1") (pin "6") (pinfunction "PWM0/RSSI_6") (pintype "output"))
      (node (ref "X3") (pin "8") (pinfunction "8_8") (pintype "passive"))
    )
    (net (code "90") (name "XBEE-9") (class "Default")
      (node (ref "U1") (pin "9") (pinfunction "~{DTR}/SLEEP_RQ/DI8_9") (pintype "bidirectional"))
      (node (ref "X3") (pin "6") (pinfunction "6_6") (pintype "passive"))
    )
    (net (code "91") (name "XBEE-11") (class "Default")
      (node (ref "U1") (pin "11") (pinfunction "RF_TX/AD4/DIO4_11") (pintype "bidirectional"))
      (node (ref "X3") (pin "2") (pinfunction "2_2") (pintype "passive"))
    )
    (net (code "92") (name "XBEE-13") (class "Default")
      (node (ref "U1") (pin "13") (pinfunction "ON/~{SLEEP}_13") (pintype "output"))
      (node (ref "X3") (pin "4") (pinfunction "4_4") (pintype "passive"))
    )
    (net (code "93") (name "XBEE-14") (class "Default")
      (node (ref "U1") (pin "14") (pinfunction "VREF_14") (pintype "input"))
      (node (ref "X3") (pin "1") (pinfunction "1_1") (pintype "passive"))
    )
    (net (code "94") (name "XBEE-15") (class "Default")
      (node (ref "U1") (pin "15") (pinfunction "ASSOC/AD5/DIO5_15") (pintype "bidirectional"))
      (node (ref "X3") (pin "3") (pinfunction "3_3") (pintype "passive"))
    )
    (net (code "95") (name "XBEE-17") (class "Default")
      (node (ref "U1") (pin "17") (pinfunction "COORD_SEL/AD3/DIO3_17") (pintype "bidirectional"))
      (node (ref "X3") (pin "5") (pinfunction "5_5") (pintype "passive"))
    )
    (net (code "96") (name "XBEE-18") (class "Default")
      (node (ref "U1") (pin "18") (pinfunction "AD2/DIO2_18") (pintype "bidirectional"))
      (node (ref "X3") (pin "7") (pinfunction "7_7") (pintype "passive"))
    )
    (net (code "97") (name "XBEE-19") (class "Default")
      (node (ref "U1") (pin "19") (pinfunction "AD1/DIO1_19") (pintype "bidirectional"))
      (node (ref "X3") (pin "9") (pinfunction "9_9") (pintype "passive"))
    )
    (net (code "98") (name "XBEE-20") (class "Default")
      (node (ref "U1") (pin "20") (pinfunction "AD0/DIO0_20") (pintype "bidirectional"))
      (node (ref "X3") (pin "11") (pinfunction "11_11") (pintype "passive"))
    )
    (net (code "99") (name "XBEE-CTS") (class "Default")
      (node (ref "U1") (pin "12") (pinfunction "~{CTS}/DIO7_12") (pintype "bidirectional"))
      (node (ref "X2") (pin "35") (pinfunction "S_35") (pintype "passive"))
    )
    (net (code "100") (name "XBEE-RTS") (class "Default")
      (node (ref "U1") (pin "16") (pinfunction "~{RTS}/AD6/DIO6_16") (pintype "bidirectional"))
      (node (ref "X2") (pin "33") (pinfunction "S_33") (pintype "passive"))
    )
    (net (code "101") (name "XBEE-RX") (class "Default")
      (node (ref "U1") (pin "2") (pinfunction "DOUT_2") (pintype "output"))
      (node (ref "X2") (pin "37") (pinfunction "S_37") (pintype "passive"))
    )
    (net (code "102") (name "XBEE-TX") (class "Default")
      (node (ref "U1") (pin "3") (pinfunction "DIN/~{CONFIG}_3") (pintype "input"))
      (node (ref "X2") (pin "39") (pinfunction "S_39") (pintype "passive"))
    )
    (net (code "103") (name "unconnected-(ULPI1-Pad6)") (class "Default")
      (node (ref "ULPI1") (pin "6") (pinfunction "6_6") (pintype "passive"))
    )
    (net (code "104") (name "unconnected-(ULPI2-Pad6)") (class "Default")
      (node (ref "ULPI2") (pin "6") (pinfunction "6_6") (pintype "passive"))
    )
  )
)
